# SW108_0713.net
KiCad netlist of a schematic drawn in Altium Designer
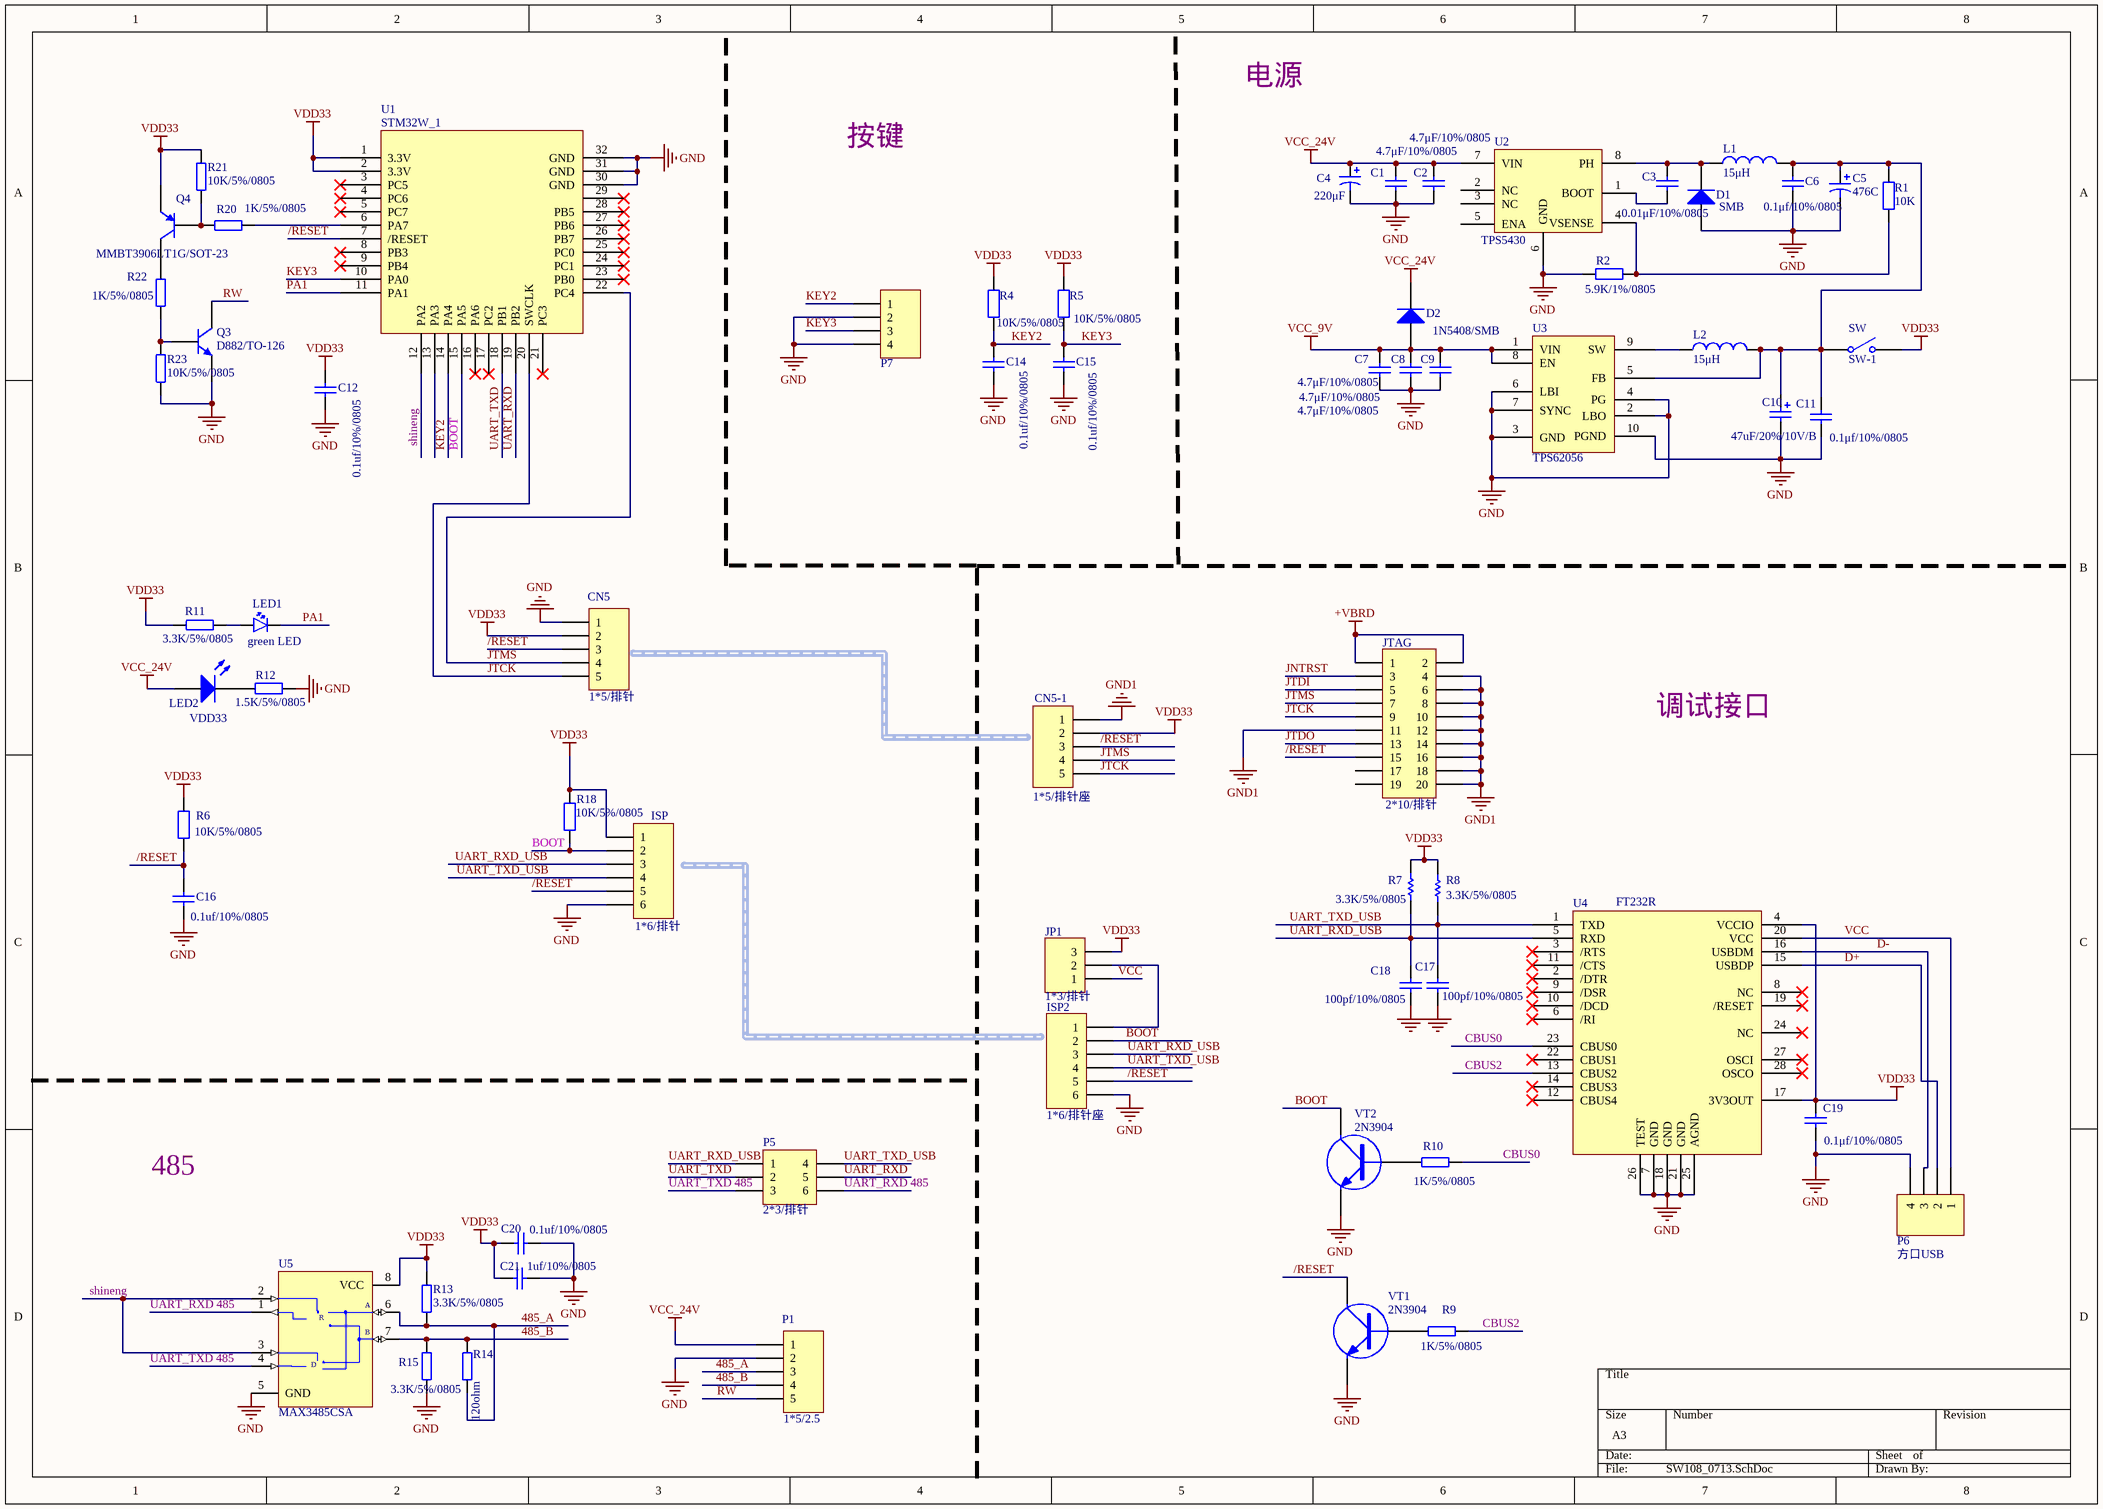
[diagram p0: SW108_0713.SchDoc]

(export (version "E")
  (design (tool "Eeschema 10.0.6"))
  (components
    (comp (ref "C1")
      (value "4.7μF/10%/0805")
      (footprint "C-0805")
      (description "Capacitor")
      (fields (field (name "PUBLISHER") "Altium Limited"))
      (libsource (lib "Miscellaneous Devices") (part "Cap"))
    )
    (comp (ref "C2")
      (value "4.7μF/10%/0805")
      (footprint "C-0805")
      (description "Capacitor")
      (fields (field (name "PUBLISHER") "Altium Limited"))
      (libsource (lib "Miscellaneous Devices") (part "Cap"))
    )
    (comp (ref "C3")
      (value "0.01μF/10%/0805")
      (footprint "C-0805")
      (description "Capacitor")
      (fields (field (name "PUBLISHER") "Altium Limited"))
      (libsource (lib "Miscellaneous Devices") (part "Cap"))
    )
    (comp (ref "C4")
      (value "220μF")
      (footprint "CZ3.0/6.5")
      (description "Polarized Capacitor (Radial)")
      (fields (field (name "PUBLISHER") "Altium Limited"))
      (libsource (lib "Miscellaneous Devices") (part "Cap Pol1"))
    )
    (comp (ref "C5")
      (value "476C")
      (footprint "C-TAN-D")
      (description "Polarized Capacitor (Radial)")
      (fields (field (name "PUBLISHER") "Altium Limited"))
      (libsource (lib "Miscellaneous Devices") (part "Cap Pol1"))
    )
    (comp (ref "C6")
      (value "0.1μf/10%/0805")
      (footprint "C-0805")
      (description "Capacitor")
      (fields (field (name "PUBLISHER") "Altium Limited"))
      (libsource (lib "Miscellaneous Devices") (part "Cap"))
    )
    (comp (ref "C7")
      (value "4.7μF/10%/0805")
      (footprint "C-0805")
      (description "Capacitor")
      (fields (field (name "PUBLISHER") "Altium Limited"))
      (libsource (lib "Miscellaneous Devices") (part "Cap"))
    )
    (comp (ref "C8")
      (value "4.7μF/10%/0805")
      (footprint "C-0805")
      (description "Capacitor")
      (fields (field (name "PUBLISHER") "Altium Limited"))
      (libsource (lib "Miscellaneous Devices") (part "Cap"))
    )
    (comp (ref "C9")
      (value "4.7μF/10%/0805")
      (footprint "C-0805")
      (description "Capacitor")
      (fields (field (name "PUBLISHER") "Altium Limited"))
      (libsource (lib "Miscellaneous Devices") (part "Cap"))
    )
    (comp (ref "C10")
      (value "47uF/20%/10V/B")
      (footprint "C-TAN-B")
      (libsource (lib "浙江关西电机数据库") (part "CAP_polarity"))
    )
    (comp (ref "C11")
      (value "0.1μf/10%/0805")
      (footprint "C-0805")
      (description "Capacitor")
      (fields (field (name "PUBLISHER") "Altium Limited"))
      (libsource (lib "Miscellaneous Devices") (part "Cap"))
    )
    (comp (ref "C12")
      (value "0.1uf/10%/0805")
      (footprint "C-0805")
      (description "Capacitor")
      (fields (field (name "PUBLISHER") "Altium Limited"))
      (libsource (lib "Miscellaneous Devices") (part "Cap"))
    )
    (comp (ref "C14")
      (value "0.1uf/10%/0805")
      (footprint "C-0805")
      (description "Capacitor")
      (fields (field (name "PUBLISHER") "Altium Limited"))
      (libsource (lib "Miscellaneous Devices") (part "Cap"))
    )
    (comp (ref "C15")
      (value "0.1uf/10%/0805")
      (footprint "C-0805")
      (description "Capacitor")
      (fields (field (name "PUBLISHER") "Altium Limited"))
      (libsource (lib "Miscellaneous Devices") (part "Cap"))
    )
    (comp (ref "C16")
      (value "0.1uf/10%/0805")
      (footprint "C-0805")
      (description "Capacitor")
      (fields (field (name "PUBLISHER") "Altium Limited"))
      (libsource (lib "Miscellaneous Devices") (part "Cap"))
    )
    (comp (ref "C17")
      (value "100pf/10%/0805")
      (footprint "C-0805")
      (description "Capacitor")
      (fields (field (name "PUBLISHER") "Altium Limited"))
      (libsource (lib "Miscellaneous Devices") (part "Cap"))
    )
    (comp (ref "C18")
      (value "100pf/10%/0805")
      (footprint "C-0805")
      (description "Capacitor")
      (fields (field (name "PUBLISHER") "Altium Limited"))
      (libsource (lib "Miscellaneous Devices") (part "Cap"))
    )
    (comp (ref "C19")
      (value "0.1μf/10%/0805")
      (footprint "C-0805")
      (description "Capacitor")
      (fields (field (name "PUBLISHER") "Altium Limited"))
      (libsource (lib "Miscellaneous Devices") (part "Cap"))
    )
    (comp (ref "C20")
      (value "0.1uf/10%/0805")
      (footprint "C-0805")
      (description "Capacitor")
      (fields (field (name "PUBLISHER") "Altium Limited"))
      (libsource (lib "Miscellaneous Devices") (part "Cap"))
    )
    (comp (ref "C21")
      (value "1uf/10%/0805")
      (footprint "C-0805")
      (description "Capacitor")
      (fields (field (name "PUBLISHER") "Altium Limited"))
      (libsource (lib "Miscellaneous Devices") (part "Cap"))
    )
    (comp (ref "CN5") (value "1*5/排针") (footprint "PIN-S-2.54-1*5") (libsource (lib "") (part "Header1*5_1")))
    (comp (ref "CN5-1")
      (value "1*5/排针座")
      (footprint "PIN-S-2.54-1*5")
      (libsource (lib "SCHLIBRARIES") (part "Header1*5"))
    )
    (comp (ref "D1")
      (value "SMB")
      (footprint "SMB")
      (description "3 Amp Medium Power Silicon Rectifier Diode")
      (fields (field (name "PUBLISHER") "Altium Limited"))
      (libsource (lib "Miscellaneous Devices") (part "Diode 1N5408"))
    )
    (comp (ref "D2")
      (value "1N5408/SMB")
      (footprint "smb")
      (description "3 Amp Medium Power Silicon Rectifier Diode")
      (fields (field (name "PUBLISHER") "Altium Limited"))
      (libsource (lib "Miscellaneous Devices") (part "Diode 1N5408"))
    )
    (comp (ref "ISP")
      (value "1*6/排针")
      (footprint "PIN-S-2.54-1*6")
      (libsource (lib "SCHLIBRARIES") (part "Header1*6"))
    )
    (comp (ref "ISP2")
      (value "1*6/排针座")
      (footprint "PIN-S-2.54-1*6")
      (libsource (lib "") (part "Header1*6_1"))
    )
    (comp (ref "JP1")
      (value "1*3/排针")
      (footprint "PIN-S-2.54-1*3")
      (libsource (lib "SCHLIBRARIES") (part "Header1*3"))
    )
    (comp (ref "JTAG")
      (value "2*10/排针")
      (footprint "IDC-20")
      (libsource (lib "SCHLIBRARIES") (part "Header2*10"))
    )
    (comp (ref "L1")
      (value "15μH")
      (footprint "GSDS104C2")
      (description "Inductor")
      (fields (field (name "PUBLISHER") "Altium Limited"))
      (libsource (lib "Miscellaneous Devices") (part "Inductor"))
    )
    (comp (ref "L2")
      (value "15μH")
      (footprint "GSDS104C2")
      (description "Inductor")
      (fields (field (name "PUBLISHER") "Altium Limited"))
      (libsource (lib "Miscellaneous Devices") (part "Inductor"))
    )
    (comp (ref "LED1") (value "green LED") (footprint "LED-φ3") (libsource (lib "Haze") (part "LED")))
    (comp (ref "LED2")
      (value "VDD33")
      (footprint "LED-φ3")
      (description "Typical BLUE SiC LED")
      (fields (field (name "PUBLISHER") "Altium Limited"))
      (libsource (lib "Miscellaneous Devices") (part "LED3"))
    )
    (comp (ref "P1") (value "1*5/2.5") (footprint "PIN-S-2.54-1*5") (libsource (lib "") (part "Header1*5_1")))
    (comp (ref "P5")
      (value "2*3/排针")
      (footprint "HDR2X3_CEN")
      (description "Header, 3-Pin, Dual row")
      (fields (field (name "PUBLISHER") "Altium Limited"))
      (libsource (lib "Miscellaneous Connectors") (part "Header 3X2A"))
    )
    (comp (ref "P6")
      (value "方口USB")
      (footprint "USB_B_90D")
      (description "Header, 4-Pin")
      (fields (field (name "PUBLISHER") "Altium Limited"))
      (libsource (lib "Miscellaneous Connectors") (part "Header 4"))
    )
    (comp (ref "P7")
      (value "Header1*4")
      (footprint "PIN-S-2.54-1*4")
      (libsource (lib "SCHLIBRARIES") (part "Header1*4"))
    )
    (comp (ref "Q3")
      (value "D882/TO-126")
      (footprint "TO-126")
      (libsource (lib "SCHLIBRARIES") (part "NPN-1E2C3B"))
    )
    (comp (ref "Q4")
      (value "MMBT3906LT1G/SOT-23")
      (footprint "SOT-23")
      (fields (field (name "PART NUMBER") "ASQ-0009BA") (field (name "型号") "MMBT3906LT1G/SOT-23"))
      (libsource (lib "浙江关西电机数据库") (part "PNP_1B2E3C"))
    )
    (comp (ref "R1")
      (value "10K")
      (footprint "R-0805")
      (description "Resistor")
      (fields (field (name "PUBLISHER") "Altium Limited"))
      (libsource (lib "Miscellaneous Devices") (part "Res2"))
    )
    (comp (ref "R2")
      (value "5.9K/1%/0805")
      (footprint "R-0805")
      (description "Resistor")
      (fields (field (name "PUBLISHER") "Altium Limited"))
      (libsource (lib "") (part "Res2_1"))
    )
    (comp (ref "R4")
      (value "10K/5%/0805")
      (footprint "R-0805")
      (description "Resistor")
      (fields (field (name "PUBLISHER") "Altium Limited"))
      (libsource (lib "Miscellaneous Devices") (part "Res2"))
    )
    (comp (ref "R5")
      (value "10K/5%/0805")
      (footprint "R-0805")
      (description "Resistor")
      (fields (field (name "PUBLISHER") "Altium Limited"))
      (libsource (lib "Miscellaneous Devices") (part "Res2"))
    )
    (comp (ref "R6")
      (value "10K/5%/0805")
      (footprint "R-0805")
      (description "Resistor")
      (fields (field (name "PUBLISHER") "Altium Limited"))
      (libsource (lib "Miscellaneous Devices") (part "Res2"))
    )
    (comp (ref "R7")
      (value "3.3K/5%/0805")
      (footprint "R-0805")
      (libsource (lib "SCHLIBRARIES") (part "RES_1"))
    )
    (comp (ref "R8")
      (value "3.3K/5%/0805")
      (footprint "R-0805")
      (libsource (lib "SCHLIBRARIES") (part "RES_1"))
    )
    (comp (ref "R9")
      (value "1K/5%/0805")
      (footprint "R-0805")
      (description "R")
      (libsource (lib "Haze") (part "RES"))
    )
    (comp (ref "R10")
      (value "1K/5%/0805")
      (footprint "R-0805")
      (description "R")
      (libsource (lib "Haze") (part "RES"))
    )
    (comp (ref "R11")
      (value "3.3K/5%/0805")
      (footprint "R-0805")
      (description "R")
      (libsource (lib "Haze") (part "RES"))
    )
    (comp (ref "R12")
      (value "1.5K/5%/0805")
      (footprint "R-0805")
      (description "Resistor")
      (fields (field (name "PUBLISHER") "Altium Limited"))
      (libsource (lib "") (part "Res2_1"))
    )
    (comp (ref "R13")
      (value "3.3K/5%/0805")
      (footprint "R-0805")
      (description "R")
      (libsource (lib "Haze") (part "RES"))
    )
    (comp (ref "R14")
      (value "120ohm")
      (footprint "R-0805")
      (description "R")
      (libsource (lib "Haze") (part "RES"))
    )
    (comp (ref "R15")
      (value "3.3K/5%/0805")
      (footprint "R-0805")
      (description "R")
      (libsource (lib "Haze") (part "RES"))
    )
    (comp (ref "R18")
      (value "10K/5%/0805")
      (footprint "R-0805")
      (description "Resistor")
      (fields (field (name "PUBLISHER") "Altium Limited"))
      (libsource (lib "Miscellaneous Devices") (part "Res2"))
    )
    (comp (ref "R20")
      (value "1K/5%/0805")
      (footprint "R-0805")
      (description "R")
      (libsource (lib "Haze") (part "RES"))
    )
    (comp (ref "R21")
      (value "10K/5%/0805")
      (footprint "R-0805")
      (description "R")
      (libsource (lib "Haze") (part "RES"))
    )
    (comp (ref "R22")
      (value "1K/5%/0805")
      (footprint "R-0805")
      (description "R")
      (libsource (lib "Haze") (part "RES"))
    )
    (comp (ref "R23")
      (value "10K/5%/0805")
      (footprint "R-0805")
      (description "R")
      (libsource (lib "Haze") (part "RES"))
    )
    (comp (ref "SW")
      (value "SW-1")
      (footprint "PIN-S-2.54-1*2")
      (libsource (lib "SCHLIBRARIES") (part "SW-1"))
    )
    (comp (ref "U1")
      (value "STM32W_1")
      (footprint "STM32W108-3")
      (libsource (lib "STM32W108-3") (part "STM32W108-3"))
    )
    (comp (ref "U2") (value "TPS5430") (footprint "SO-G8") (libsource (lib "SCHLIBRARIES") (part "TPS5430")))
    (comp (ref "U3")
      (value "TPS62056")
      (footprint "MSOP-10")
      (libsource (lib "SCHLIBRARIES") (part "TPS62056"))
    )
    (comp (ref "U4") (value "FT232R") (footprint "SSOP-28") (libsource (lib "Haze") (part "FT232R")))
    (comp (ref "U5")
      (value "MAX3485CSA")
      (footprint "SO-G8")
      (description "Low-Power, Slew-Rate-Limited RS-485/RS-422 Transceiver")
      (fields (field (name "PUBLISHER") "Altium Limited"))
      (libsource (lib "Maxim Communication Transceiver") (part "MAX485CSA"))
    )
    (comp (ref "VT1")
      (value "2N3904")
      (footprint "SOT23-3")
      (description "NPN Transistor")
      (libsource (lib "Haze") (part "NPN"))
    )
    (comp (ref "VT2")
      (value "2N3904")
      (footprint "SOT23-3")
      (description "NPN Transistor")
      (libsource (lib "Haze") (part "NPN"))
    )
  )
  (nets
    (net (code "1") (name "+VBRD") (class "Default")
      (node (ref "JTAG") (pin "1") (pinfunction "1_1") (pintype "passive"))
      (node (ref "JTAG") (pin "2") (pinfunction "2_2") (pintype "passive"))
    )
    (net (code "2") (name "/485_A") (class "Default")
      (node (ref "P1") (pin "3") (pinfunction "3_3") (pintype "passive"))
      (node (ref "R13") (pin "1") (pinfunction "1_1") (pintype "passive"))
      (node (ref "R14") (pin "2") (pinfunction "2_2") (pintype "passive"))
      (node (ref "U5") (pin "6") (pinfunction "A_6") (pintype "bidirectional"))
    )
    (net (code "3") (name "/485_B") (class "Default")
      (node (ref "P1") (pin "4") (pinfunction "4_4") (pintype "passive"))
      (node (ref "R14") (pin "1") (pinfunction "1_1") (pintype "passive"))
      (node (ref "R15") (pin "2") (pinfunction "2_2") (pintype "passive"))
      (node (ref "U5") (pin "7") (pinfunction "B_7") (pintype "bidirectional"))
    )
    (net (code "4") (name "/BOOT") (class "Default")
      (node (ref "ISP") (pin "2") (pinfunction "2_2") (pintype "passive"))
      (node (ref "ISP2") (pin "2") (pinfunction "2_2") (pintype "passive"))
      (node (ref "R18") (pin "1") (pinfunction "1_1") (pintype "passive"))
      (node (ref "U1") (pin "15") (pinfunction "PA5_15") (pintype "passive"))
      (node (ref "VT2") (pin "3") (pinfunction "C_3") (pintype "passive"))
    )
    (net (code "5") (name "/CBUS0") (class "Default")
      (node (ref "R10") (pin "2") (pinfunction "2_2") (pintype "passive"))
      (node (ref "U4") (pin "23") (pinfunction "CBUS0_23") (pintype "passive"))
    )
    (net (code "6") (name "/CBUS2") (class "Default")
      (node (ref "R9") (pin "2") (pinfunction "2_2") (pintype "passive"))
      (node (ref "U4") (pin "13") (pinfunction "CBUS2_13") (pintype "passive"))
    )
    (net (code "7") (name "/D+") (class "Default")
      (node (ref "P6") (pin "2") (pinfunction "2_2") (pintype "passive"))
      (node (ref "U4") (pin "15") (pinfunction "USBDP_15") (pintype "passive"))
    )
    (net (code "8") (name "/D-") (class "Default")
      (node (ref "P6") (pin "3") (pinfunction "3_3") (pintype "passive"))
      (node (ref "U4") (pin "16") (pinfunction "USBDM_16") (pintype "passive"))
    )
    (net (code "9") (name "/JNTRST") (class "Default")
      (node (ref "JTAG") (pin "3") (pinfunction "3_3") (pintype "passive"))
    )
    (net (code "10") (name "/JTCK") (class "Default")
      (node (ref "CN5") (pin "5") (pinfunction "5_5") (pintype "passive"))
      (node (ref "CN5-1") (pin "5") (pinfunction "5_5") (pintype "passive"))
      (node (ref "JTAG") (pin "9") (pinfunction "9_9") (pintype "passive"))
      (node (ref "U1") (pin "20") (pinfunction "SWCLK_20") (pintype "passive"))
    )
    (net (code "11") (name "/JTDI") (class "Default")
      (node (ref "JTAG") (pin "5") (pinfunction "5_5") (pintype "passive"))
    )
    (net (code "12") (name "/JTDO") (class "Default")
      (node (ref "JTAG") (pin "13") (pinfunction "13_13") (pintype "passive"))
    )
    (net (code "13") (name "/JTMS") (class "Default")
      (node (ref "CN5") (pin "4") (pinfunction "4_4") (pintype "passive"))
      (node (ref "CN5-1") (pin "4") (pinfunction "4_4") (pintype "passive"))
      (node (ref "JTAG") (pin "7") (pinfunction "7_7") (pintype "passive"))
      (node (ref "U1") (pin "22") (pinfunction "PC4_22") (pintype "passive"))
    )
    (net (code "14") (name "/KEY2") (class "Default")
      (node (ref "C14") (pin "2") (pinfunction "2_2") (pintype "passive"))
      (node (ref "P7") (pin "1") (pinfunction "1_1") (pintype "passive"))
      (node (ref "R4") (pin "1") (pinfunction "1_1") (pintype "passive"))
      (node (ref "U1") (pin "14") (pinfunction "PA4_14") (pintype "passive"))
    )
    (net (code "15") (name "/KEY3") (class "Default")
      (node (ref "C15") (pin "2") (pinfunction "2_2") (pintype "passive"))
      (node (ref "P7") (pin "3") (pinfunction "3_3") (pintype "passive"))
      (node (ref "R5") (pin "1") (pinfunction "1_1") (pintype "passive"))
      (node (ref "U1") (pin "10") (pinfunction "PA0_10") (pintype "passive"))
    )
    (net (code "16") (name "/PA1") (class "Default")
      (node (ref "LED1") (pin "2") (pinfunction "K_2") (pintype "passive"))
      (node (ref "U1") (pin "11") (pinfunction "PA1_11") (pintype "passive"))
    )
    (net (code "17") (name "/RW") (class "Default")
      (node (ref "P1") (pin "5") (pinfunction "5_5") (pintype "passive"))
      (node (ref "Q3") (pin "2") (pinfunction "C_2") (pintype "passive"))
    )
    (net (code "18") (name "/UART_RXD") (class "Default")
      (node (ref "P5") (pin "5") (pinfunction "5_5") (pintype "passive"))
      (node (ref "U1") (pin "19") (pinfunction "PB2_19") (pintype "passive"))
    )
    (net (code "19") (name "/UART_RXD 485") (class "Default")
      (node (ref "P5") (pin "6") (pinfunction "6_6") (pintype "passive"))
      (node (ref "U5") (pin "1") (pinfunction "RO_1") (pintype "output"))
    )
    (net (code "20") (name "/UART_RXD_USB") (class "Default")
      (node (ref "C18") (pin "2") (pinfunction "2_2") (pintype "passive"))
      (node (ref "ISP") (pin "3") (pinfunction "3_3") (pintype "passive"))
      (node (ref "ISP2") (pin "3") (pinfunction "3_3") (pintype "passive"))
      (node (ref "P5") (pin "1") (pinfunction "1_1") (pintype "passive"))
      (node (ref "R7") (pin "1") (pinfunction "1_1") (pintype "passive"))
      (node (ref "U4") (pin "5") (pinfunction "RXD_5") (pintype "passive"))
    )
    (net (code "21") (name "/UART_TXD") (class "Default")
      (node (ref "P5") (pin "2") (pinfunction "2_2") (pintype "passive"))
      (node (ref "U1") (pin "18") (pinfunction "PB1_18") (pintype "passive"))
    )
    (net (code "22") (name "/UART_TXD 485") (class "Default")
      (node (ref "P5") (pin "3") (pinfunction "3_3") (pintype "passive"))
      (node (ref "U5") (pin "4") (pinfunction "DI_4") (pintype "input"))
    )
    (net (code "23") (name "/UART_TXD_USB") (class "Default")
      (node (ref "C17") (pin "2") (pinfunction "2_2") (pintype "passive"))
      (node (ref "ISP") (pin "4") (pinfunction "4_4") (pintype "passive"))
      (node (ref "ISP2") (pin "4") (pinfunction "4_4") (pintype "passive"))
      (node (ref "P5") (pin "4") (pinfunction "4_4") (pintype "passive"))
      (node (ref "R8") (pin "1") (pinfunction "1_1") (pintype "passive"))
      (node (ref "U4") (pin "1") (pinfunction "TXD_1") (pintype "passive"))
    )
    (net (code "24") (name "/VCC") (class "Default")
      (node (ref "JP1") (pin "1") (pinfunction "1_1") (pintype "passive"))
      (node (ref "P6") (pin "1") (pinfunction "1_1") (pintype "passive"))
      (node (ref "U4") (pin "20") (pinfunction "VCC_20") (pintype "passive"))
    )
    (net (code "25") (name "/shineng") (class "Default")
      (node (ref "U1") (pin "12") (pinfunction "PA2_12") (pintype "passive"))
      (node (ref "U5") (pin "2") (pinfunction "~{RE}_2") (pintype "input"))
      (node (ref "U5") (pin "3") (pinfunction "DE_3") (pintype "input"))
    )
    (net (code "26") (name "/{slash}RESET") (class "Default")
      (node (ref "C16") (pin "2") (pinfunction "2_2") (pintype "passive"))
      (node (ref "CN5") (pin "3") (pinfunction "3_3") (pintype "passive"))
      (node (ref "CN5-1") (pin "3") (pinfunction "3_3") (pintype "passive"))
      (node (ref "ISP") (pin "5") (pinfunction "5_5") (pintype "passive"))
      (node (ref "ISP2") (pin "5") (pinfunction "5_5") (pintype "passive"))
      (node (ref "JTAG") (pin "15") (pinfunction "15_15") (pintype "passive"))
      (node (ref "R6") (pin "1") (pinfunction "1_1") (pintype "passive"))
      (node (ref "U1") (pin "7") (pinfunction "/RESET_7") (pintype "passive"))
      (node (ref "VT1") (pin "3") (pinfunction "C_3") (pintype "passive"))
    )
    (net (code "27") (name "GND") (class "Default")
      (node (ref "C1") (pin "1") (pinfunction "1_1") (pintype "passive"))
      (node (ref "C10") (pin "2") (pinfunction "2_2") (pintype "passive"))
      (node (ref "C11") (pin "1") (pinfunction "1_1") (pintype "passive"))
      (node (ref "C12") (pin "1") (pinfunction "1_1") (pintype "passive"))
      (node (ref "C14") (pin "1") (pinfunction "1_1") (pintype "passive"))
      (node (ref "C15") (pin "1") (pinfunction "1_1") (pintype "passive"))
      (node (ref "C16") (pin "1") (pinfunction "1_1") (pintype "passive"))
      (node (ref "C17") (pin "1") (pinfunction "1_1") (pintype "passive"))
      (node (ref "C18") (pin "1") (pinfunction "1_1") (pintype "passive"))
      (node (ref "C19") (pin "1") (pinfunction "1_1") (pintype "passive"))
      (node (ref "C2") (pin "1") (pinfunction "1_1") (pintype "passive"))
      (node (ref "C20") (pin "1") (pinfunction "1_1") (pintype "passive"))
      (node (ref "C21") (pin "1") (pinfunction "1_1") (pintype "passive"))
      (node (ref "C4") (pin "2") (pinfunction "2_2") (pintype "passive"))
      (node (ref "C5") (pin "2") (pinfunction "2_2") (pintype "passive"))
      (node (ref "C6") (pin "1") (pinfunction "1_1") (pintype "passive"))
      (node (ref "C7") (pin "1") (pinfunction "1_1") (pintype "passive"))
      (node (ref "C8") (pin "1") (pinfunction "1_1") (pintype "passive"))
      (node (ref "C9") (pin "1") (pinfunction "1_1") (pintype "passive"))
      (node (ref "CN5") (pin "1") (pinfunction "1_1") (pintype "passive"))
      (node (ref "D1") (pin "1") (pinfunction "A_1") (pintype "passive"))
      (node (ref "ISP") (pin "6") (pinfunction "6_6") (pintype "passive"))
      (node (ref "ISP2") (pin "6") (pinfunction "6_6") (pintype "passive"))
      (node (ref "P1") (pin "2") (pinfunction "2_2") (pintype "passive"))
      (node (ref "P6") (pin "4") (pinfunction "4_4") (pintype "passive"))
      (node (ref "P7") (pin "2") (pinfunction "2_2") (pintype "passive"))
      (node (ref "P7") (pin "4") (pinfunction "4_4") (pintype "passive"))
      (node (ref "Q3") (pin "1") (pinfunction "E_1") (pintype "passive"))
      (node (ref "R12") (pin "1") (pinfunction "1_1") (pintype "passive"))
      (node (ref "R15") (pin "1") (pinfunction "1_1") (pintype "passive"))
      (node (ref "R2") (pin "2") (pinfunction "2_2") (pintype "passive"))
      (node (ref "R23") (pin "1") (pinfunction "1_1") (pintype "passive"))
      (node (ref "U1") (pin "30") (pinfunction "GND_30") (pintype "passive"))
      (node (ref "U1") (pin "31") (pinfunction "GND_31") (pintype "passive"))
      (node (ref "U1") (pin "32") (pinfunction "GND_32") (pintype "passive"))
      (node (ref "U2") (pin "6") (pinfunction "GND_6") (pintype "passive"))
      (node (ref "U3") (pin "10") (pinfunction "PGND_10") (pintype "passive"))
      (node (ref "U3") (pin "2") (pinfunction "LBO_2") (pintype "passive"))
      (node (ref "U3") (pin "3") (pinfunction "GND_3") (pintype "passive"))
      (node (ref "U3") (pin "4") (pinfunction "PG_4") (pintype "passive"))
      (node (ref "U3") (pin "6") (pinfunction "LBI_6") (pintype "passive"))
      (node (ref "U3") (pin "7") (pinfunction "SYNC_7") (pintype "passive"))
      (node (ref "U4") (pin "18") (pinfunction "GND_18") (pintype "passive"))
      (node (ref "U4") (pin "21") (pinfunction "GND_21") (pintype "passive"))
      (node (ref "U4") (pin "25") (pinfunction "AGND_25") (pintype "passive"))
      (node (ref "U4") (pin "26") (pinfunction "TEST_26") (pintype "passive"))
      (node (ref "U4") (pin "7") (pinfunction "GND_7") (pintype "passive"))
      (node (ref "U5") (pin "5") (pinfunction "GND_5") (pintype "power_in"))
      (node (ref "VT1") (pin "2") (pinfunction "E_2") (pintype "passive"))
      (node (ref "VT2") (pin "2") (pinfunction "E_2") (pintype "passive"))
    )
    (net (code "28") (name "GND1") (class "Default")
      (node (ref "CN5-1") (pin "1") (pinfunction "1_1") (pintype "passive"))
      (node (ref "JTAG") (pin "10") (pinfunction "10_10") (pintype "passive"))
      (node (ref "JTAG") (pin "11") (pinfunction "11_11") (pintype "passive"))
      (node (ref "JTAG") (pin "12") (pinfunction "12_12") (pintype "passive"))
      (node (ref "JTAG") (pin "14") (pinfunction "14_14") (pintype "passive"))
      (node (ref "JTAG") (pin "16") (pinfunction "16_16") (pintype "passive"))
      (node (ref "JTAG") (pin "18") (pinfunction "18_18") (pintype "passive"))
      (node (ref "JTAG") (pin "20") (pinfunction "20_20") (pintype "passive"))
      (node (ref "JTAG") (pin "4") (pinfunction "4_4") (pintype "passive"))
      (node (ref "JTAG") (pin "6") (pinfunction "6_6") (pintype "passive"))
      (node (ref "JTAG") (pin "8") (pinfunction "8_8") (pintype "passive"))
    )
    (net (code "29") (name "Net-(D1-K)") (class "Default")
      (node (ref "C3") (pin "2") (pinfunction "2_2") (pintype "passive"))
      (node (ref "D1") (pin "2") (pinfunction "K_2") (pintype "passive"))
      (node (ref "L1") (pin "1") (pinfunction "1_1") (pintype "passive"))
      (node (ref "U2") (pin "8") (pinfunction "PH_8") (pintype "passive"))
    )
    (net (code "30") (name "Net-(ISP2-Pad1)") (class "Default")
      (node (ref "ISP2") (pin "1") (pinfunction "1_1") (pintype "passive"))
      (node (ref "JP1") (pin "2") (pinfunction "2_2") (pintype "passive"))
    )
    (net (code "31") (name "Net-(LED1-A)") (class "Default")
      (node (ref "LED1") (pin "1") (pinfunction "A_1") (pintype "passive"))
      (node (ref "R11") (pin "2") (pinfunction "2_2") (pintype "passive"))
    )
    (net (code "32") (name "Net-(LED2-K)") (class "Default")
      (node (ref "LED2") (pin "2") (pinfunction "K_2") (pintype "passive"))
      (node (ref "R12") (pin "2") (pinfunction "2_2") (pintype "passive"))
    )
    (net (code "33") (name "Net-(Q3-B)") (class "Default")
      (node (ref "Q3") (pin "3") (pinfunction "B_3") (pintype "passive"))
      (node (ref "R22") (pin "1") (pinfunction "1_1") (pintype "passive"))
      (node (ref "R23") (pin "2") (pinfunction "2_2") (pintype "passive"))
    )
    (net (code "34") (name "Net-(Q4-B)") (class "Default")
      (node (ref "Q4") (pin "1") (pinfunction "B_1") (pintype "passive"))
      (node (ref "R20") (pin "1") (pinfunction "1_1") (pintype "passive"))
      (node (ref "R21") (pin "1") (pinfunction "1_1") (pintype "passive"))
    )
    (net (code "35") (name "Net-(Q4-C)") (class "Default")
      (node (ref "Q4") (pin "3") (pinfunction "C_3") (pintype "passive"))
      (node (ref "R22") (pin "2") (pinfunction "2_2") (pintype "passive"))
    )
    (net (code "36") (name "Net-(U1-PA7)") (class "Default")
      (node (ref "R20") (pin "2") (pinfunction "2_2") (pintype "passive"))
      (node (ref "U1") (pin "6") (pinfunction "PA7_6") (pintype "passive"))
    )
    (net (code "37") (name "Net-(U2-BOOT)") (class "Default")
      (node (ref "C3") (pin "1") (pinfunction "1_1") (pintype "passive"))
      (node (ref "U2") (pin "1") (pinfunction "BOOT_1") (pintype "passive"))
    )
    (net (code "38") (name "Net-(U2-VSENSE)") (class "Default")
      (node (ref "R1") (pin "1") (pinfunction "1_1") (pintype "passive"))
      (node (ref "R2") (pin "1") (pinfunction "1_1") (pintype "passive"))
      (node (ref "U2") (pin "4") (pinfunction "VSENSE_4") (pintype "passive"))
    )
    (net (code "39") (name "Net-(U3-FB)") (class "Default")
      (node (ref "C10") (pin "1") (pinfunction "1_1") (pintype "passive"))
      (node (ref "C11") (pin "2") (pinfunction "2_2") (pintype "passive"))
      (node (ref "C5") (pin "1") (pinfunction "1_1") (pintype "passive"))
      (node (ref "C6") (pin "2") (pinfunction "2_2") (pintype "passive"))
      (node (ref "L1") (pin "2") (pinfunction "2_2") (pintype "passive"))
      (node (ref "L2") (pin "2") (pinfunction "2_2") (pintype "passive"))
      (node (ref "R1") (pin "2") (pinfunction "2_2") (pintype "passive"))
      (node (ref "SW") (pin "1") (pinfunction "1_1") (pintype "passive"))
      (node (ref "U3") (pin "5") (pinfunction "FB_5") (pintype "passive"))
    )
    (net (code "40") (name "Net-(U3-SW)") (class "Default")
      (node (ref "L2") (pin "1") (pinfunction "1_1") (pintype "passive"))
      (node (ref "U3") (pin "9") (pinfunction "SW_9") (pintype "passive"))
    )
    (net (code "41") (name "Net-(VT1-B)") (class "Default")
      (node (ref "R9") (pin "1") (pinfunction "1_1") (pintype "passive"))
      (node (ref "VT1") (pin "1") (pinfunction "B_1") (pintype "passive"))
    )
    (net (code "42") (name "Net-(VT2-B)") (class "Default")
      (node (ref "R10") (pin "1") (pinfunction "1_1") (pintype "passive"))
      (node (ref "VT2") (pin "1") (pinfunction "B_1") (pintype "passive"))
    )
    (net (code "43") (name "VCC_9V") (class "Default")
      (node (ref "C7") (pin "2") (pinfunction "2_2") (pintype "passive"))
      (node (ref "C8") (pin "2") (pinfunction "2_2") (pintype "passive"))
      (node (ref "C9") (pin "2") (pinfunction "2_2") (pintype "passive"))
      (node (ref "D2") (pin "1") (pinfunction "A_1") (pintype "passive"))
      (node (ref "U3") (pin "1") (pinfunction "VIN_1") (pintype "passive"))
      (node (ref "U3") (pin "8") (pinfunction "EN_8") (pintype "passive"))
    )
    (net (code "44") (name "VCC_24V") (class "Default")
      (node (ref "C1") (pin "2") (pinfunction "2_2") (pintype "passive"))
      (node (ref "C2") (pin "2") (pinfunction "2_2") (pintype "passive"))
      (node (ref "C4") (pin "1") (pinfunction "1_1") (pintype "passive"))
      (node (ref "D2") (pin "2") (pinfunction "K_2") (pintype "passive"))
      (node (ref "LED2") (pin "1") (pinfunction "A_1") (pintype "passive"))
      (node (ref "P1") (pin "1") (pinfunction "1_1") (pintype "passive"))
      (node (ref "U2") (pin "7") (pinfunction "VIN_7") (pintype "passive"))
    )
    (net (code "45") (name "VDD33") (class "Default")
      (node (ref "C12") (pin "2") (pinfunction "2_2") (pintype "passive"))
      (node (ref "C19") (pin "2") (pinfunction "2_2") (pintype "passive"))
      (node (ref "C20") (pin "2") (pinfunction "2_2") (pintype "passive"))
      (node (ref "C21") (pin "2") (pinfunction "2_2") (pintype "passive"))
      (node (ref "CN5") (pin "2") (pinfunction "2_2") (pintype "passive"))
      (node (ref "CN5-1") (pin "2") (pinfunction "2_2") (pintype "passive"))
      (node (ref "ISP") (pin "1") (pinfunction "1_1") (pintype "passive"))
      (node (ref "JP1") (pin "3") (pinfunction "3_3") (pintype "passive"))
      (node (ref "Q4") (pin "2") (pinfunction "E_2") (pintype "passive"))
      (node (ref "R11") (pin "1") (pinfunction "1_1") (pintype "passive"))
      (node (ref "R13") (pin "2") (pinfunction "2_2") (pintype "passive"))
      (node (ref "R18") (pin "2") (pinfunction "2_2") (pintype "passive"))
      (node (ref "R21") (pin "2") (pinfunction "2_2") (pintype "passive"))
      (node (ref "R4") (pin "2") (pinfunction "2_2") (pintype "passive"))
      (node (ref "R5") (pin "2") (pinfunction "2_2") (pintype "passive"))
      (node (ref "R6") (pin "2") (pinfunction "2_2") (pintype "passive"))
      (node (ref "R7") (pin "2") (pinfunction "2_2") (pintype "passive"))
      (node (ref "R8") (pin "2") (pinfunction "2_2") (pintype "passive"))
      (node (ref "SW") (pin "2") (pinfunction "2_2") (pintype "passive"))
      (node (ref "U1") (pin "1") (pinfunction "3.3V_1") (pintype "passive"))
      (node (ref "U1") (pin "2") (pinfunction "3.3V_2") (pintype "passive"))
      (node (ref "U4") (pin "17") (pinfunction "3V3OUT_17") (pintype "passive"))
      (node (ref "U4") (pin "4") (pinfunction "VCCIO_4") (pintype "passive"))
      (node (ref "U5") (pin "8") (pinfunction "VCC_8") (pintype "power_in"))
    )
    (net (code "46") (name "unconnected-(JTAG-Pad17)") (class "Default")
      (node (ref "JTAG") (pin "17") (pinfunction "17_17") (pintype "passive"))
    )
    (net (code "47") (name "unconnected-(JTAG-Pad19)") (class "Default")
      (node (ref "JTAG") (pin "19") (pinfunction "19_19") (pintype "passive"))
    )
    (net (code "48") (name "unconnected-(U1-PA3-Pad13)") (class "Default")
      (node (ref "U1") (pin "13") (pinfunction "PA3_13") (pintype "passive"))
    )
    (net (code "49") (name "unconnected-(U1-PA6-Pad16)") (class "Default")
      (node (ref "U1") (pin "16") (pinfunction "PA6_16") (pintype "passive+no_connect"))
    )
    (net (code "50") (name "unconnected-(U1-PB0-Pad23)") (class "Default")
      (node (ref "U1") (pin "23") (pinfunction "PB0_23") (pintype "passive+no_connect"))
    )
    (net (code "51") (name "unconnected-(U1-PB3-Pad8)") (class "Default")
      (node (ref "U1") (pin "8") (pinfunction "PB3_8") (pintype "passive+no_connect"))
    )
    (net (code "52") (name "unconnected-(U1-PB4-Pad9)") (class "Default")
      (node (ref "U1") (pin "9") (pinfunction "PB4_9") (pintype "passive+no_connect"))
    )
    (net (code "53") (name "unconnected-(U1-PB5-Pad28)") (class "Default")
      (node (ref "U1") (pin "28") (pinfunction "PB5_28") (pintype "passive+no_connect"))
    )
    (net (code "54") (name "unconnected-(U1-PB6-Pad27)") (class "Default")
      (node (ref "U1") (pin "27") (pinfunction "PB6_27") (pintype "passive+no_connect"))
    )
    (net (code "55") (name "unconnected-(U1-PB7-Pad26)") (class "Default")
      (node (ref "U1") (pin "26") (pinfunction "PB7_26") (pintype "passive+no_connect"))
    )
    (net (code "56") (name "unconnected-(U1-PC0-Pad25)") (class "Default")
      (node (ref "U1") (pin "25") (pinfunction "PC0_25") (pintype "passive+no_connect"))
    )
    (net (code "57") (name "unconnected-(U1-PC1-Pad24)") (class "Default")
      (node (ref "U1") (pin "24") (pinfunction "PC1_24") (pintype "passive+no_connect"))
    )
    (net (code "58") (name "unconnected-(U1-PC2-Pad17)") (class "Default")
      (node (ref "U1") (pin "17") (pinfunction "PC2_17") (pintype "passive+no_connect"))
    )
    (net (code "59") (name "unconnected-(U1-PC3-Pad21)") (class "Default")
      (node (ref "U1") (pin "21") (pinfunction "PC3_21") (pintype "passive+no_connect"))
    )
    (net (code "60") (name "unconnected-(U1-PC5-Pad3)") (class "Default")
      (node (ref "U1") (pin "3") (pinfunction "PC5_3") (pintype "passive+no_connect"))
    )
    (net (code "61") (name "unconnected-(U1-PC6-Pad4)") (class "Default")
      (node (ref "U1") (pin "4") (pinfunction "PC6_4") (pintype "passive+no_connect"))
    )
    (net (code "62") (name "unconnected-(U1-PC7-Pad5)") (class "Default")
      (node (ref "U1") (pin "5") (pinfunction "PC7_5") (pintype "passive+no_connect"))
    )
    (net (code "63") (name "unconnected-(U1-Pad29)") (class "Default")
      (node (ref "U1") (pin "29") (pintype "passive+no_connect"))
    )
    (net (code "64") (name "unconnected-(U2-ENA-Pad5)") (class "Default")
      (node (ref "U2") (pin "5") (pinfunction "ENA_5") (pintype "passive"))
    )
    (net (code "65") (name "unconnected-(U2-NC-Pad2)") (class "Default")
      (node (ref "U2") (pin "2") (pinfunction "NC_2") (pintype "passive"))
    )
    (net (code "66") (name "unconnected-(U2-NC-Pad3)") (class "Default")
      (node (ref "U2") (pin "3") (pinfunction "NC_3") (pintype "passive"))
    )
    (net (code "67") (name "unconnected-(U4-CBUS1-Pad22)") (class "Default")
      (node (ref "U4") (pin "22") (pinfunction "CBUS1_22") (pintype "passive+no_connect"))
    )
    (net (code "68") (name "unconnected-(U4-CBUS3-Pad14)") (class "Default")
      (node (ref "U4") (pin "14") (pinfunction "CBUS3_14") (pintype "passive+no_connect"))
    )
    (net (code "69") (name "unconnected-(U4-CBUS4-Pad12)") (class "Default")
      (node (ref "U4") (pin "12") (pinfunction "CBUS4_12") (pintype "passive+no_connect"))
    )
    (net (code "70") (name "unconnected-(U4-NC-Pad8)") (class "Default")
      (node (ref "U4") (pin "8") (pinfunction "NC_8") (pintype "passive+no_connect"))
    )
    (net (code "71") (name "unconnected-(U4-NC-Pad24)") (class "Default")
      (node (ref "U4") (pin "24") (pinfunction "NC_24") (pintype "passive+no_connect"))
    )
    (net (code "72") (name "unconnected-(U4-OSCI-Pad27)") (class "Default")
      (node (ref "U4") (pin "27") (pinfunction "OSCI_27") (pintype "passive+no_connect"))
    )
    (net (code "73") (name "unconnected-(U4-OSCO-Pad28)") (class "Default")
      (node (ref "U4") (pin "28") (pinfunction "OSCO_28") (pintype "passive+no_connect"))
    )
    (net (code "74") (name "unconnected-(U4-{slash}CTS-Pad11)") (class "Default")
      (node (ref "U4") (pin "11") (pinfunction "/CTS_11") (pintype "passive+no_connect"))
    )
    (net (code "75") (name "unconnected-(U4-{slash}DCD-Pad10)") (class "Default")
      (node (ref "U4") (pin "10") (pinfunction "/DCD_10") (pintype "passive+no_connect"))
    )
    (net (code "76") (name "unconnected-(U4-{slash}DSR-Pad9)") (class "Default")
      (node (ref "U4") (pin "9") (pinfunction "/DSR_9") (pintype "passive+no_connect"))
    )
    (net (code "77") (name "unconnected-(U4-{slash}DTR-Pad2)") (class "Default")
      (node (ref "U4") (pin "2") (pinfunction "/DTR_2") (pintype "passive+no_connect"))
    )
    (net (code "78") (name "unconnected-(U4-{slash}RESET-Pad19)") (class "Default")
      (node (ref "U4") (pin "19") (pinfunction "/RESET_19") (pintype "passive+no_connect"))
    )
    (net (code "79") (name "unconnected-(U4-{slash}RI-Pad6)") (class "Default")
      (node (ref "U4") (pin "6") (pinfunction "/RI_6") (pintype "passive+no_connect"))
    )
    (net (code "80") (name "unconnected-(U4-{slash}RTS-Pad3)") (class "Default")
      (node (ref "U4") (pin "3") (pinfunction "/RTS_3") (pintype "passive+no_connect"))
    )
  )
)
